# RF.net
KiCad netlist of a schematic drawn in Altium Designer
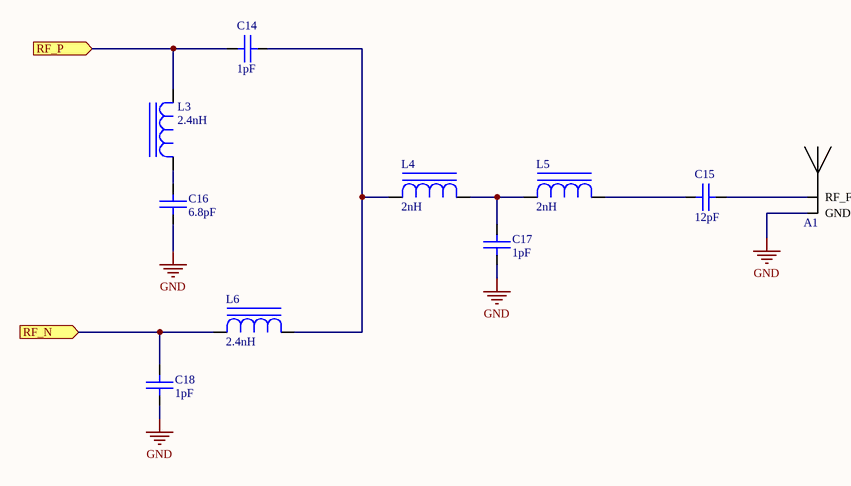
[diagram p0: RF.SchDoc]

(export (version "E")
  (design (tool "Eeschema 10.0.6"))
  (components
    (comp (ref "A1")
      (value "Antenna Wi-Fi")
      (footprint "Antenna_WiFi")
      (description "2.43GHz")
      (libsource (lib "gprs_modem_2") (part "Antenna Wi-Fi"))
    )
    (comp (ref "C14") (value "1pF") (footprint "CC0402") (libsource (lib "gprs_modem_2") (part "CC0402")))
    (comp (ref "C15") (value "12pF") (footprint "CC0402") (libsource (lib "gprs_modem_2") (part "CC0402")))
    (comp (ref "C16") (value "6.8pF") (footprint "CC0402") (libsource (lib "gprs_modem_2") (part "CC0402")))
    (comp (ref "C17") (value "1pF") (footprint "CC0402") (libsource (lib "gprs_modem_2") (part "CC0402")))
    (comp (ref "C18") (value "1pF") (footprint "CC0402") (libsource (lib "gprs_modem_2") (part "CC0402")))
    (comp (ref "L3")
      (value "2.4nH")
      (footprint "L0402")
      (description "L0402")
      (libsource (lib "gprs_modem_2") (part "L0402"))
    )
    (comp (ref "L4")
      (value "2nH")
      (footprint "L0402")
      (description "L0402")
      (libsource (lib "gprs_modem_2") (part "L0402"))
    )
    (comp (ref "L5")
      (value "2nH")
      (footprint "L0402")
      (description "L0402")
      (libsource (lib "gprs_modem_2") (part "L0402"))
    )
    (comp (ref "L6")
      (value "2.4nH")
      (footprint "L0402")
      (description "L0402")
      (libsource (lib "gprs_modem_2") (part "L0402"))
    )
  )
  (nets
    (net (code "1") (name "/RF_N") (class "Default")
      (node (ref "C18") (pin "2") (pinfunction "B_2") (pintype "passive"))
      (node (ref "L6") (pin "1") (pinfunction "A_1") (pintype "passive"))
    )
    (net (code "2") (name "/RF_P") (class "Default")
      (node (ref "C14") (pin "2") (pinfunction "B_2") (pintype "passive"))
      (node (ref "L3") (pin "2") (pinfunction "C_2") (pintype "passive"))
    )
    (net (code "3") (name "GND") (class "Default")
      (node (ref "A1") (pin "2") (pinfunction "GND_2") (pintype "passive"))
      (node (ref "C16") (pin "1") (pinfunction "A_1") (pintype "passive"))
      (node (ref "C17") (pin "1") (pinfunction "A_1") (pintype "passive"))
      (node (ref "C18") (pin "1") (pinfunction "A_1") (pintype "passive"))
    )
    (net (code "4") (name "Net-(A1-RF_Feed)") (class "Default")
      (node (ref "A1") (pin "1") (pinfunction "RF_Feed_1") (pintype "passive"))
      (node (ref "C15") (pin "2") (pinfunction "B_2") (pintype "passive"))
    )
    (net (code "5") (name "Net-(C14-A)") (class "Default")
      (node (ref "C14") (pin "1") (pinfunction "A_1") (pintype "passive"))
      (node (ref "L4") (pin "1") (pinfunction "A_1") (pintype "passive"))
      (node (ref "L6") (pin "2") (pinfunction "C_2") (pintype "passive"))
    )
    (net (code "6") (name "Net-(C15-A)") (class "Default")
      (node (ref "C15") (pin "1") (pinfunction "A_1") (pintype "passive"))
      (node (ref "L5") (pin "2") (pinfunction "C_2") (pintype "passive"))
    )
    (net (code "7") (name "Net-(C16-B)") (class "Default")
      (node (ref "C16") (pin "2") (pinfunction "B_2") (pintype "passive"))
      (node (ref "L3") (pin "1") (pinfunction "A_1") (pintype "passive"))
    )
    (net (code "8") (name "Net-(C17-B)") (class "Default")
      (node (ref "C17") (pin "2") (pinfunction "B_2") (pintype "passive"))
      (node (ref "L4") (pin "2") (pinfunction "C_2") (pintype "passive"))
      (node (ref "L5") (pin "1") (pinfunction "A_1") (pintype "passive"))
    )
  )
)
